# mainboard.net
KiCad netlist of a schematic drawn in EAGLE
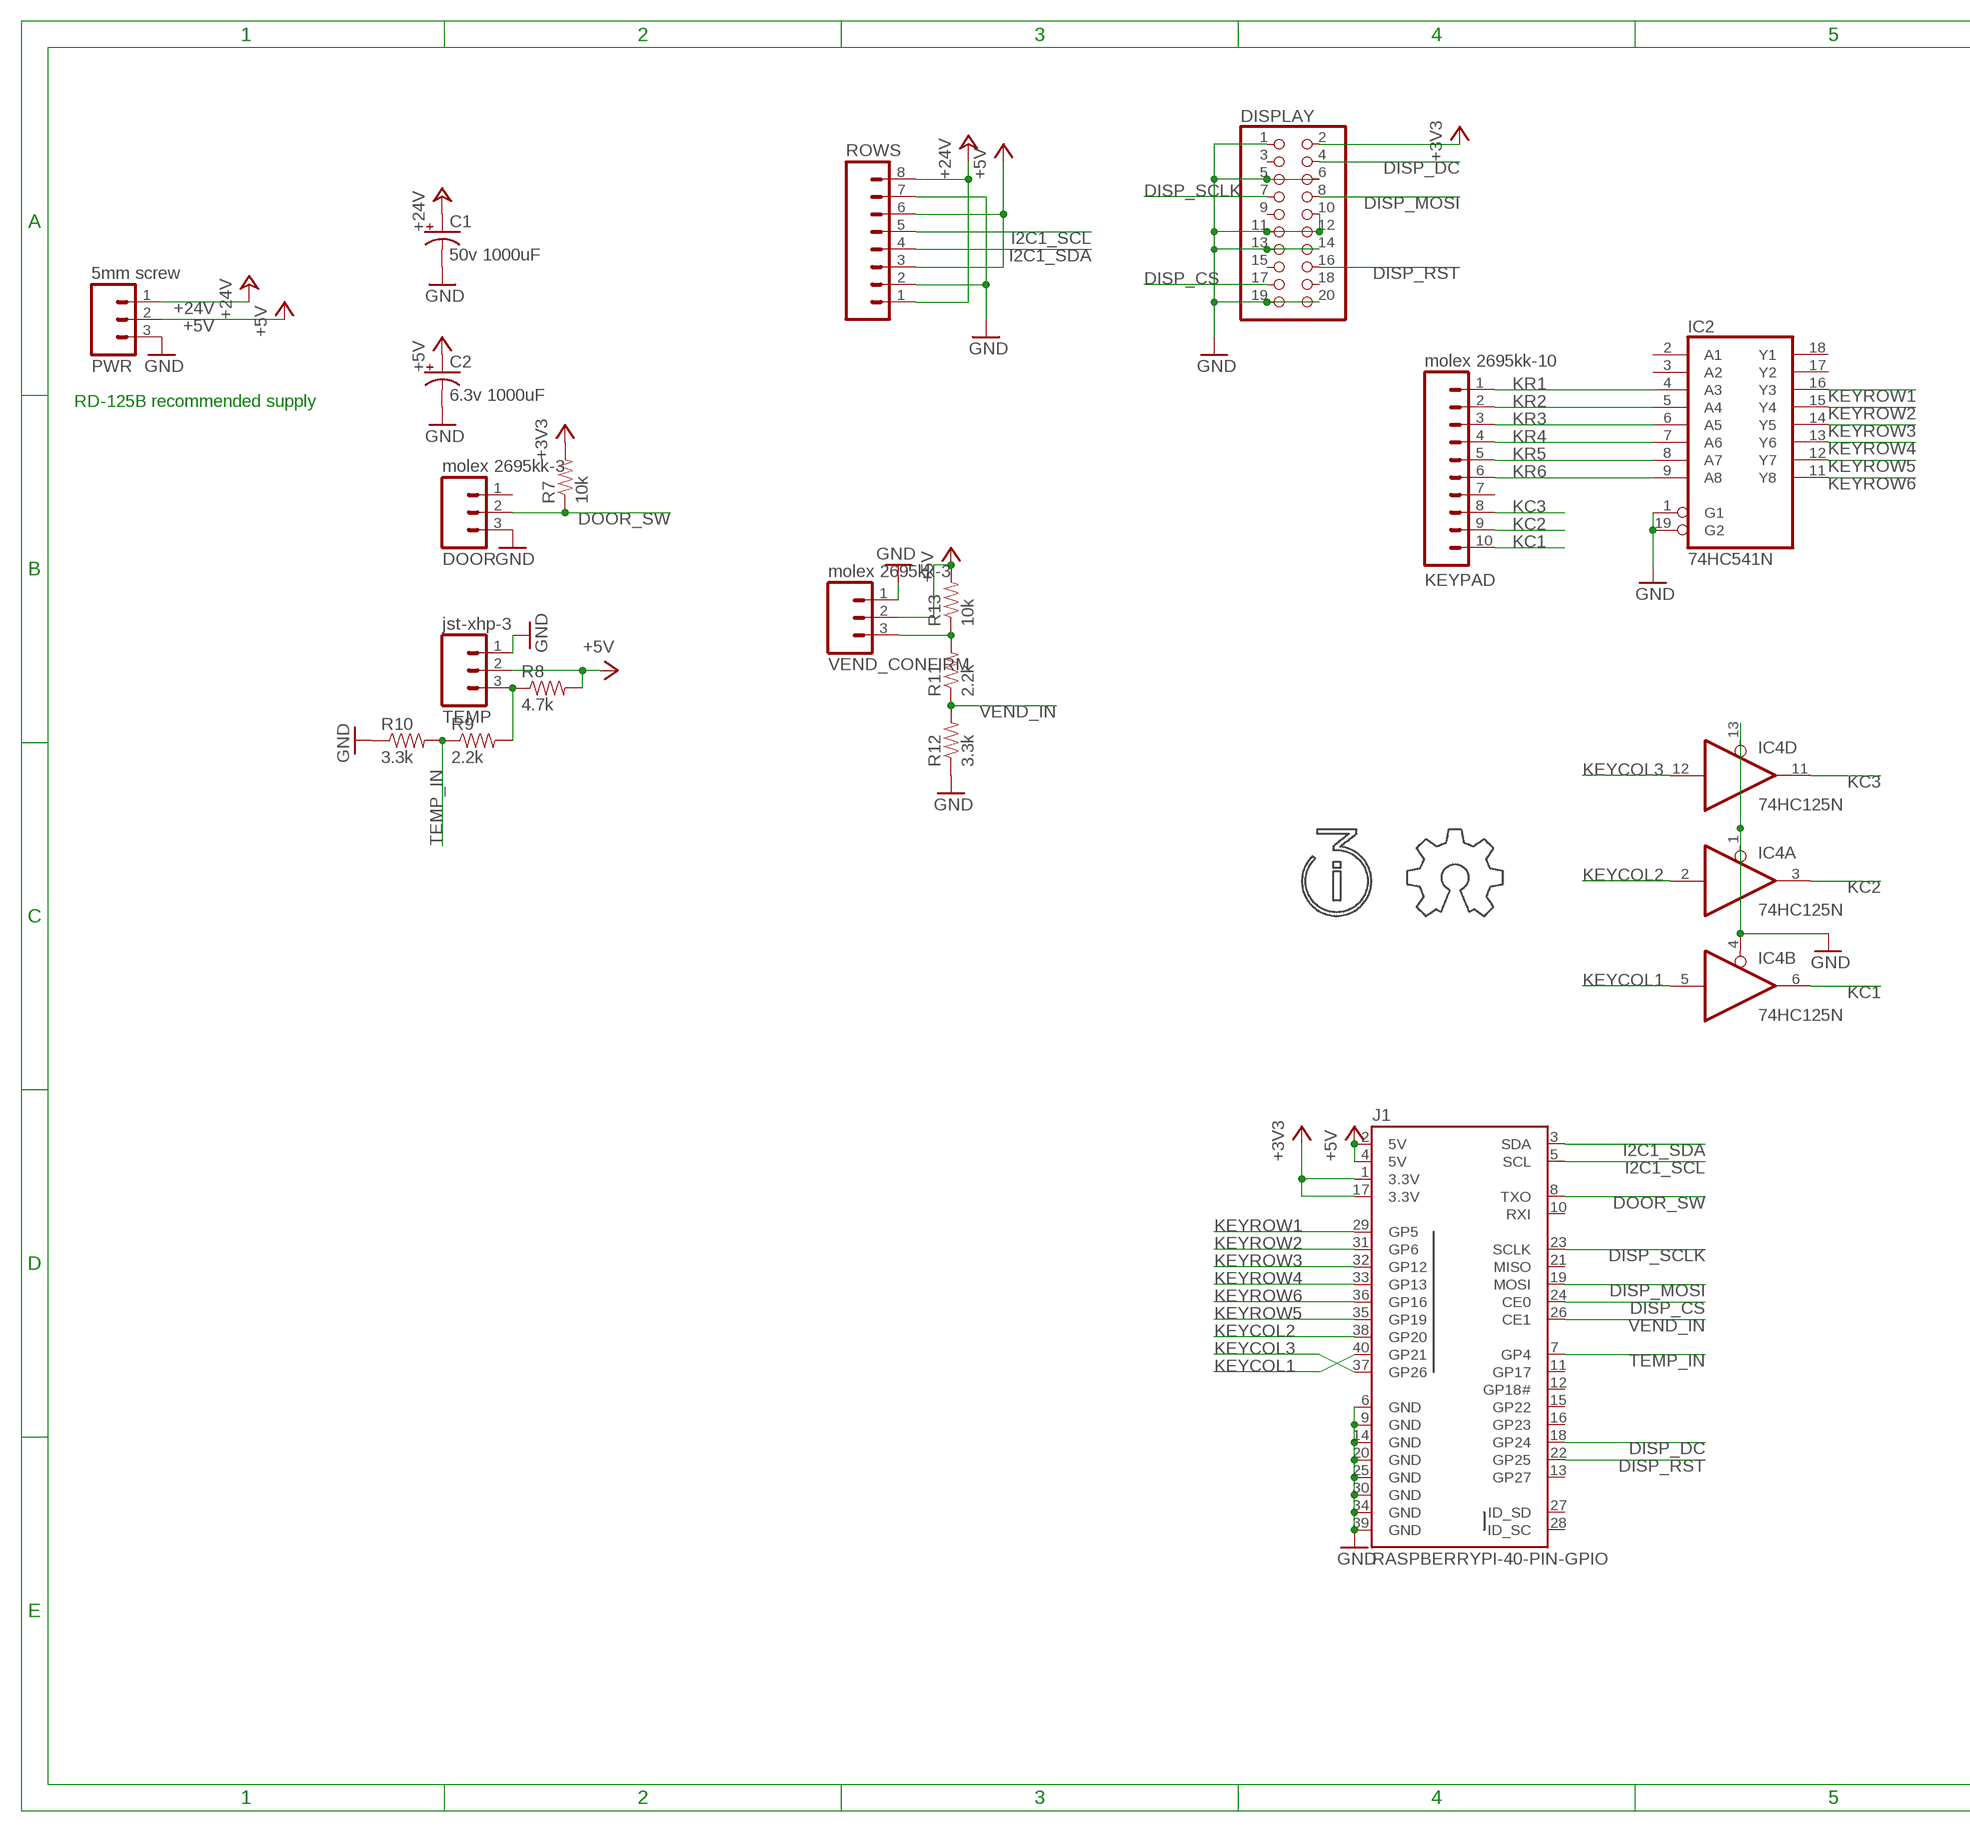
[diagram p0: schematic, sheet 1, part 1 of 2]
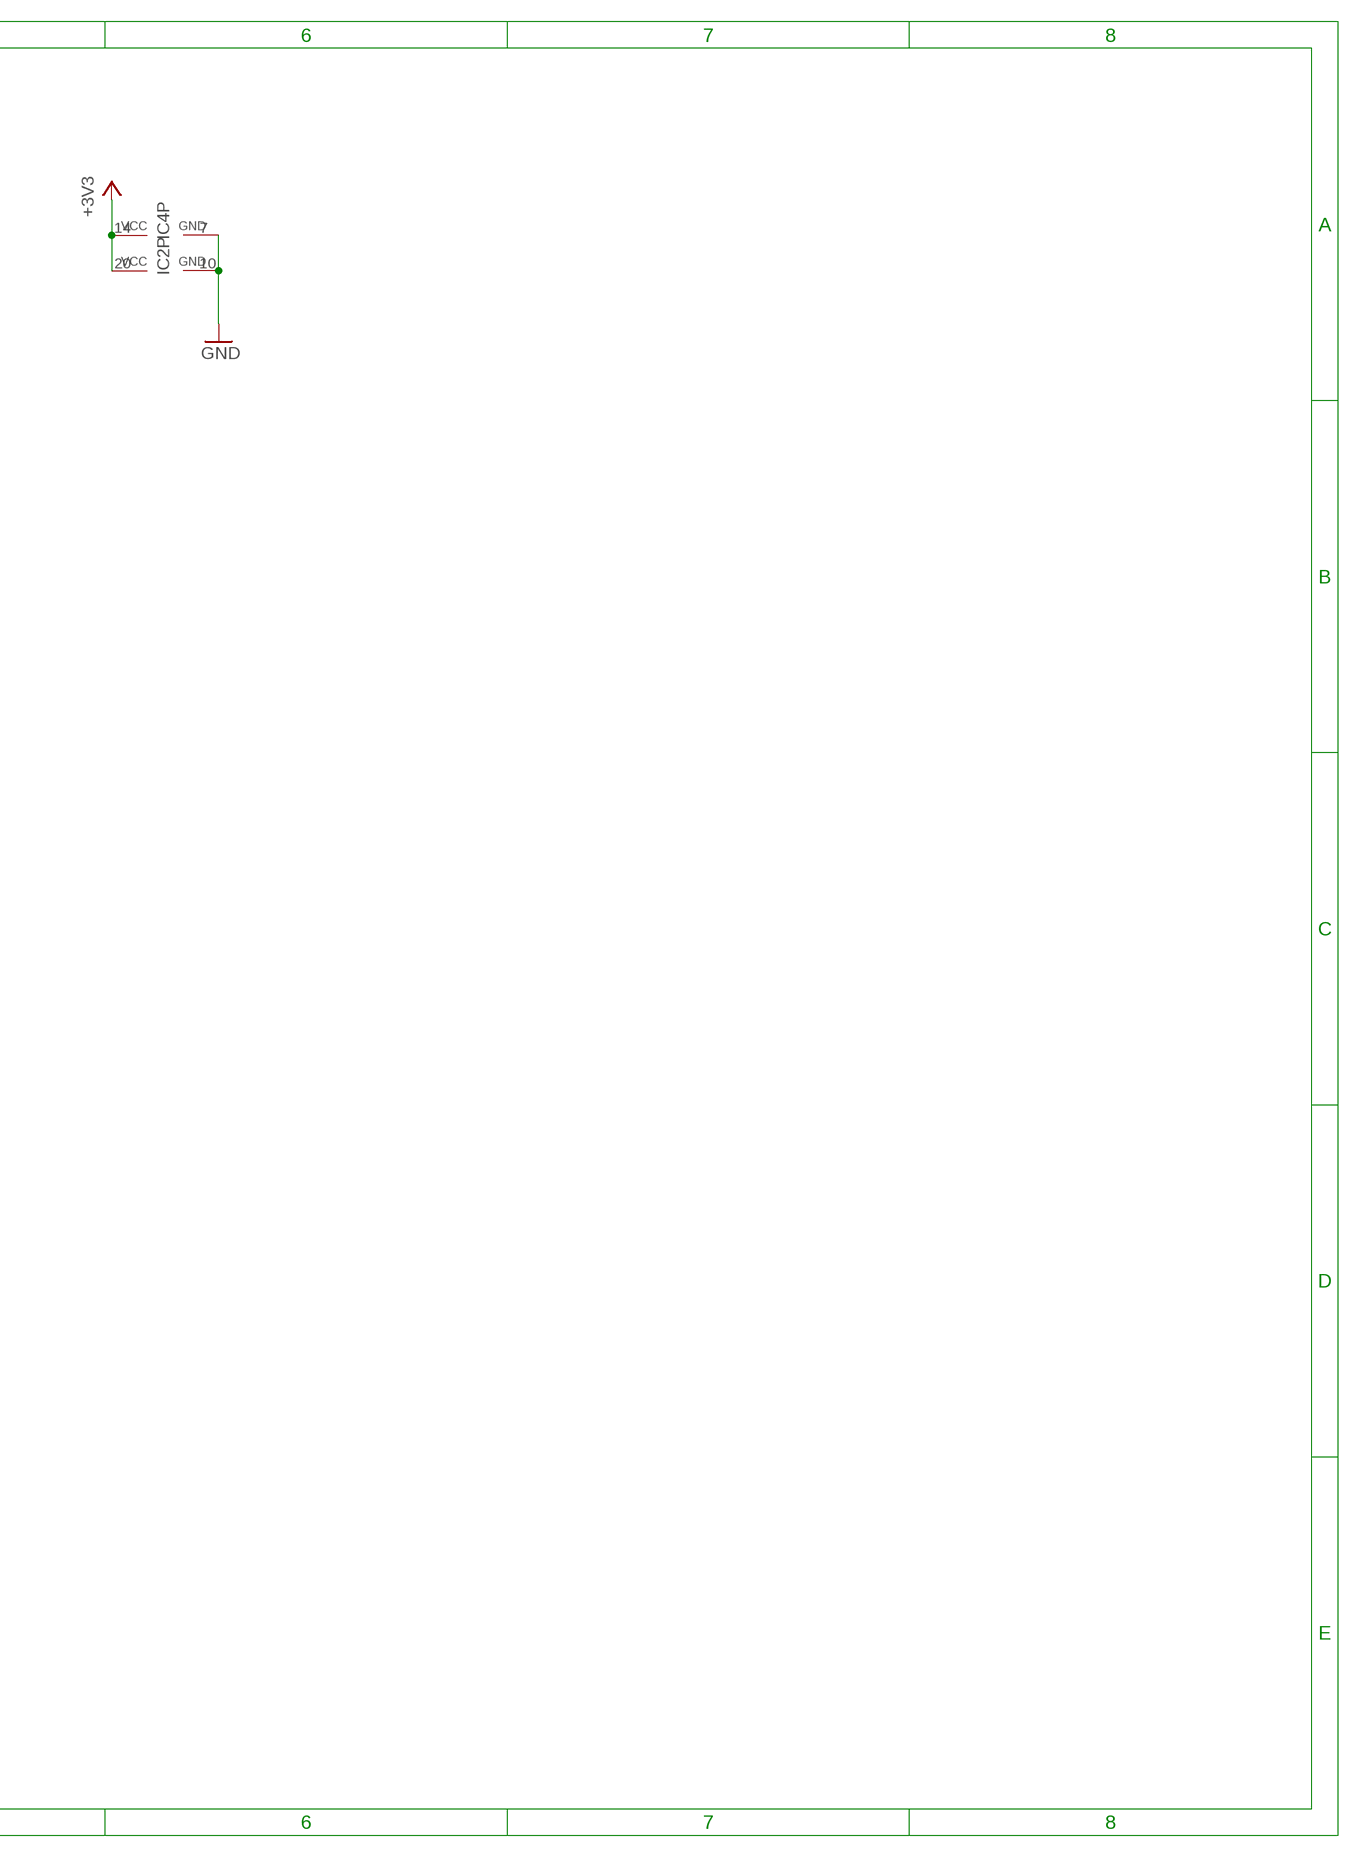
[diagram p1: schematic, sheet 1, part 2 of 2]

(export (version "E")
  (design (tool "Eeschema 10.0.6"))
  (components
    (comp (ref "C1")
      (value "50v 1000uF")
      (footprint "eagle-import:CPOL-RADIAL-1000UF-25V")
      (libsource (lib "eagle-import") (part "CAP_POLPTH4"))
    )
    (comp (ref "C2")
      (value "6.3v 1000uF")
      (footprint "eagle-import:CPOL-RADIAL-1000UF-25V")
      (libsource (lib "eagle-import") (part "CAP_POLPTH4"))
    )
    (comp (ref "DISPLAY")
      (value "PINHD-2X10")
      (footprint "eagle-import:2X10")
      (libsource (lib "eagle-import") (part "PINHD-2X10"))
    )
    (comp (ref "DOOR")
      (value "molex 2695kk-3")
      (footprint "eagle-import:MOLEX-1X3")
      (libsource (lib "eagle-import") (part "M03POLAR"))
    )
    (comp (ref "IC2")
      (value "74HC541N")
      (footprint "eagle-import:DIL20")
      (libsource (lib "eagle-import") (part "74541NHC"))
    )
    (comp (ref "IC4")
      (value "74HC125N")
      (footprint "eagle-import:DIL14")
      (libsource (lib "eagle-import") (part "74125NHC"))
    )
    (comp (ref "J1")
      (value "RASPBERRYPI-40-PIN-GPIO")
      (footprint "eagle-import:2X20-SHROUDED")
      (libsource (lib "eagle-import") (part "RASPBERRYPI-40-PIN-GPIO"))
    )
    (comp (ref "KEYPAD")
      (value "molex 2695kk-10")
      (footprint "eagle-import:1X10_LOCK")
      (libsource (lib "eagle-import") (part "M10LOCK"))
    )
    (comp (ref "PWR")
      (value "5mm screw")
      (footprint "eagle-import:SCREWTERMINAL-5MM-3")
      (libsource (lib "eagle-import") (part "M03-SCREW-5MM"))
    )
    (comp (ref "R7")
      (value "10k")
      (footprint "eagle-import:1206")
      (libsource (lib "eagle-import") (part "RESISTOR1206"))
    )
    (comp (ref "R8")
      (value "4.7k")
      (footprint "eagle-import:1206")
      (libsource (lib "eagle-import") (part "RESISTOR1206"))
    )
    (comp (ref "R9")
      (value "2.2k")
      (footprint "eagle-import:1206")
      (libsource (lib "eagle-import") (part "RESISTOR1206"))
    )
    (comp (ref "R10")
      (value "3.3k")
      (footprint "eagle-import:1206")
      (libsource (lib "eagle-import") (part "RESISTOR1206"))
    )
    (comp (ref "R11")
      (value "2.2k")
      (footprint "eagle-import:1206")
      (libsource (lib "eagle-import") (part "RESISTOR1206"))
    )
    (comp (ref "R12")
      (value "3.3k")
      (footprint "eagle-import:1206")
      (libsource (lib "eagle-import") (part "RESISTOR1206"))
    )
    (comp (ref "R13")
      (value "10k")
      (footprint "eagle-import:1206")
      (libsource (lib "eagle-import") (part "RESISTOR1206"))
    )
    (comp (ref "ROWS")
      (value "M08FEMALE_LOCK")
      (footprint "eagle-import:1X08_FEMALE_LOCK")
      (libsource (lib "eagle-import") (part "M08FEMALE_LOCK"))
    )
    (comp (ref "TEMP")
      (value "jst-xhp-3")
      (footprint "eagle-import:1X03")
      (libsource (lib "eagle-import") (part "M03PTH"))
    )
    (comp (ref "U$1")
      (value "I3LOGO")
      (footprint "eagle-import:I3LOGO")
      (libsource (lib "eagle-import") (part "I3LOGO"))
    )
    (comp (ref "U$2")
      (value "OSHWLOGO")
      (footprint "eagle-import:OSHWLOGO")
      (libsource (lib "eagle-import") (part "OSHWLOGO"))
    )
    (comp (ref "VEND_CONFIRM")
      (value "molex 2695kk-3")
      (footprint "eagle-import:MOLEX-1X3")
      (libsource (lib "eagle-import") (part "M03POLAR"))
    )
  )
  (nets
    (net (code "1") (name "+3V3") (class "Default")
      (node (ref "DISPLAY") (pin "2") (pinfunction "2_2") (pintype "passive"))
      (node (ref "IC2") (pin "20") (pinfunction "VCC_20") (pintype "power_in"))
      (node (ref "IC4") (pin "14") (pinfunction "VCC_14") (pintype "power_in"))
      (node (ref "J1") (pin "1") (pinfunction "3.3V_1") (pintype "power_in"))
      (node (ref "J1") (pin "17") (pinfunction "3.3V_17") (pintype "power_in"))
      (node (ref "R7") (pin "2") (pinfunction "2_2") (pintype "passive"))
    )
    (net (code "2") (name "+5V") (class "Default")
      (node (ref "C2") (pin "+") (pinfunction "+_+") (pintype "passive"))
      (node (ref "J1") (pin "2") (pinfunction "5V_2") (pintype "power_in"))
      (node (ref "J1") (pin "4") (pinfunction "5V_4") (pintype "power_in"))
      (node (ref "PWR") (pin "2") (pinfunction "2_2") (pintype "passive"))
      (node (ref "R13") (pin "2") (pinfunction "2_2") (pintype "passive"))
      (node (ref "R8") (pin "2") (pinfunction "2_2") (pintype "passive"))
      (node (ref "ROWS") (pin "3") (pinfunction "3_3") (pintype "passive"))
      (node (ref "ROWS") (pin "6") (pinfunction "6_6") (pintype "passive"))
      (node (ref "TEMP") (pin "2") (pinfunction "2_2") (pintype "passive"))
      (node (ref "VEND_CONFIRM") (pin "2") (pinfunction "2_2") (pintype "passive"))
    )
    (net (code "3") (name "+24V") (class "Default")
      (node (ref "C1") (pin "+") (pinfunction "+_+") (pintype "passive"))
      (node (ref "PWR") (pin "1") (pinfunction "1_1") (pintype "passive"))
      (node (ref "ROWS") (pin "1") (pinfunction "1_1") (pintype "passive"))
      (node (ref "ROWS") (pin "8") (pinfunction "8_8") (pintype "passive"))
    )
    (net (code "4") (name "/DISP_CS") (class "Default")
      (node (ref "DISPLAY") (pin "17") (pinfunction "17_17") (pintype "passive"))
      (node (ref "J1") (pin "24") (pinfunction "CE0_24") (pintype "output"))
    )
    (net (code "5") (name "/DISP_DC") (class "Default")
      (node (ref "DISPLAY") (pin "4") (pinfunction "4_4") (pintype "passive"))
      (node (ref "J1") (pin "18") (pinfunction "GP24_18") (pintype "bidirectional"))
    )
    (net (code "6") (name "/DISP_MOSI") (class "Default")
      (node (ref "DISPLAY") (pin "8") (pinfunction "8_8") (pintype "passive"))
      (node (ref "J1") (pin "19") (pinfunction "MOSI_19") (pintype "output"))
    )
    (net (code "7") (name "/DISP_RST") (class "Default")
      (node (ref "DISPLAY") (pin "16") (pinfunction "16_16") (pintype "passive"))
      (node (ref "J1") (pin "22") (pinfunction "GP25_22") (pintype "bidirectional"))
    )
    (net (code "8") (name "/DISP_SCLK") (class "Default")
      (node (ref "DISPLAY") (pin "7") (pinfunction "7_7") (pintype "passive"))
      (node (ref "J1") (pin "23") (pinfunction "SCLK_23") (pintype "output"))
    )
    (net (code "9") (name "/DOOR_SW") (class "Default")
      (node (ref "DOOR") (pin "2") (pinfunction "2_2") (pintype "passive"))
      (node (ref "J1") (pin "8") (pinfunction "TXO_8") (pintype "output"))
      (node (ref "R7") (pin "1") (pinfunction "1_1") (pintype "passive"))
    )
    (net (code "10") (name "/I2C1_SCL") (class "Default")
      (node (ref "J1") (pin "5") (pinfunction "SCL_5") (pintype "bidirectional"))
      (node (ref "ROWS") (pin "5") (pinfunction "5_5") (pintype "passive"))
    )
    (net (code "11") (name "/I2C1_SDA") (class "Default")
      (node (ref "J1") (pin "3") (pinfunction "SDA_3") (pintype "bidirectional"))
      (node (ref "ROWS") (pin "4") (pinfunction "4_4") (pintype "passive"))
    )
    (net (code "12") (name "/KC1") (class "Default")
      (node (ref "IC4") (pin "6") (pinfunction "O_6") (pintype "tri_state"))
      (node (ref "KEYPAD") (pin "10") (pinfunction "10_10") (pintype "passive"))
    )
    (net (code "13") (name "/KC2") (class "Default")
      (node (ref "IC4") (pin "3") (pinfunction "O_3") (pintype "tri_state"))
      (node (ref "KEYPAD") (pin "9") (pinfunction "9_9") (pintype "passive"))
    )
    (net (code "14") (name "/KC3") (class "Default")
      (node (ref "IC4") (pin "11") (pinfunction "O_11") (pintype "tri_state"))
      (node (ref "KEYPAD") (pin "8") (pinfunction "8_8") (pintype "passive"))
    )
    (net (code "15") (name "/KEYCOL1") (class "Default")
      (node (ref "IC4") (pin "5") (pinfunction "I_5") (pintype "input"))
      (node (ref "J1") (pin "40") (pinfunction "GP21_40") (pintype "bidirectional"))
    )
    (net (code "16") (name "/KEYCOL2") (class "Default")
      (node (ref "IC4") (pin "2") (pinfunction "I_2") (pintype "input"))
      (node (ref "J1") (pin "38") (pinfunction "GP20_38") (pintype "bidirectional"))
    )
    (net (code "17") (name "/KEYCOL3") (class "Default")
      (node (ref "IC4") (pin "12") (pinfunction "I_12") (pintype "input"))
      (node (ref "J1") (pin "37") (pinfunction "GP26_37") (pintype "bidirectional"))
    )
    (net (code "18") (name "/KEYROW1") (class "Default")
      (node (ref "IC2") (pin "16") (pinfunction "Y3_16") (pintype "tri_state"))
      (node (ref "J1") (pin "29") (pinfunction "GP5_29") (pintype "bidirectional"))
    )
    (net (code "19") (name "/KEYROW2") (class "Default")
      (node (ref "IC2") (pin "15") (pinfunction "Y4_15") (pintype "tri_state"))
      (node (ref "J1") (pin "31") (pinfunction "GP6_31") (pintype "bidirectional"))
    )
    (net (code "20") (name "/KEYROW3") (class "Default")
      (node (ref "IC2") (pin "14") (pinfunction "Y5_14") (pintype "tri_state"))
      (node (ref "J1") (pin "32") (pinfunction "GP12_32") (pintype "bidirectional"))
    )
    (net (code "21") (name "/KEYROW4") (class "Default")
      (node (ref "IC2") (pin "13") (pinfunction "Y6_13") (pintype "tri_state"))
      (node (ref "J1") (pin "33") (pinfunction "GP13_33") (pintype "bidirectional"))
    )
    (net (code "22") (name "/KEYROW5") (class "Default")
      (node (ref "IC2") (pin "12") (pinfunction "Y7_12") (pintype "tri_state"))
      (node (ref "J1") (pin "35") (pinfunction "GP19_35") (pintype "bidirectional"))
    )
    (net (code "23") (name "/KEYROW6") (class "Default")
      (node (ref "IC2") (pin "11") (pinfunction "Y8_11") (pintype "tri_state"))
      (node (ref "J1") (pin "36") (pinfunction "GP16_36") (pintype "bidirectional"))
    )
    (net (code "24") (name "/KR1") (class "Default")
      (node (ref "IC2") (pin "4") (pinfunction "A3_4") (pintype "input"))
      (node (ref "KEYPAD") (pin "1") (pinfunction "1_1") (pintype "passive"))
    )
    (net (code "25") (name "/KR2") (class "Default")
      (node (ref "IC2") (pin "5") (pinfunction "A4_5") (pintype "input"))
      (node (ref "KEYPAD") (pin "2") (pinfunction "2_2") (pintype "passive"))
    )
    (net (code "26") (name "/KR3") (class "Default")
      (node (ref "IC2") (pin "6") (pinfunction "A5_6") (pintype "input"))
      (node (ref "KEYPAD") (pin "3") (pinfunction "3_3") (pintype "passive"))
    )
    (net (code "27") (name "/KR4") (class "Default")
      (node (ref "IC2") (pin "7") (pinfunction "A6_7") (pintype "input"))
      (node (ref "KEYPAD") (pin "4") (pinfunction "4_4") (pintype "passive"))
    )
    (net (code "28") (name "/KR5") (class "Default")
      (node (ref "IC2") (pin "8") (pinfunction "A7_8") (pintype "input"))
      (node (ref "KEYPAD") (pin "5") (pinfunction "5_5") (pintype "passive"))
    )
    (net (code "29") (name "/KR6") (class "Default")
      (node (ref "IC2") (pin "9") (pinfunction "A8_9") (pintype "input"))
      (node (ref "KEYPAD") (pin "6") (pinfunction "6_6") (pintype "passive"))
    )
    (net (code "30") (name "/TEMP_IN") (class "Default")
      (node (ref "J1") (pin "7") (pinfunction "GP4_7") (pintype "bidirectional"))
      (node (ref "R10") (pin "2") (pinfunction "2_2") (pintype "passive"))
      (node (ref "R9") (pin "1") (pinfunction "1_1") (pintype "passive"))
    )
    (net (code "31") (name "/VEND_IN") (class "Default")
      (node (ref "J1") (pin "26") (pinfunction "CE1_26") (pintype "output"))
      (node (ref "R11") (pin "1") (pinfunction "1_1") (pintype "passive"))
      (node (ref "R12") (pin "2") (pinfunction "2_2") (pintype "passive"))
    )
    (net (code "32") (name "GND") (class "Default")
      (node (ref "C1") (pin "-") (pinfunction "-_-") (pintype "passive"))
      (node (ref "C2") (pin "-") (pinfunction "-_-") (pintype "passive"))
      (node (ref "DISPLAY") (pin "1") (pinfunction "1_1") (pintype "passive"))
      (node (ref "DISPLAY") (pin "10") (pinfunction "10_10") (pintype "passive"))
      (node (ref "DISPLAY") (pin "11") (pinfunction "11_11") (pintype "passive"))
      (node (ref "DISPLAY") (pin "12") (pinfunction "12_12") (pintype "passive"))
      (node (ref "DISPLAY") (pin "13") (pinfunction "13_13") (pintype "passive"))
      (node (ref "DISPLAY") (pin "14") (pinfunction "14_14") (pintype "passive"))
      (node (ref "DISPLAY") (pin "19") (pinfunction "19_19") (pintype "passive"))
      (node (ref "DISPLAY") (pin "20") (pinfunction "20_20") (pintype "passive"))
      (node (ref "DISPLAY") (pin "5") (pinfunction "5_5") (pintype "passive"))
      (node (ref "DISPLAY") (pin "6") (pinfunction "6_6") (pintype "passive"))
      (node (ref "DOOR") (pin "3") (pinfunction "3_3") (pintype "passive"))
      (node (ref "IC2") (pin "1") (pinfunction "G1_1") (pintype "input"))
      (node (ref "IC2") (pin "10") (pinfunction "GND_10") (pintype "power_in"))
      (node (ref "IC2") (pin "19") (pinfunction "G2_19") (pintype "input"))
      (node (ref "IC4") (pin "1") (pinfunction "OE_1") (pintype "input"))
      (node (ref "IC4") (pin "13") (pinfunction "OE_13") (pintype "input"))
      (node (ref "IC4") (pin "4") (pinfunction "OE_4") (pintype "input"))
      (node (ref "IC4") (pin "7") (pinfunction "GND_7") (pintype "power_in"))
      (node (ref "J1") (pin "14") (pinfunction "GND_14") (pintype "power_in"))
      (node (ref "J1") (pin "20") (pinfunction "GND_20") (pintype "power_in"))
      (node (ref "J1") (pin "25") (pinfunction "GND_25") (pintype "power_in"))
      (node (ref "J1") (pin "30") (pinfunction "GND_30") (pintype "power_in"))
      (node (ref "J1") (pin "34") (pinfunction "GND_34") (pintype "power_in"))
      (node (ref "J1") (pin "39") (pinfunction "GND_39") (pintype "power_in"))
      (node (ref "J1") (pin "6") (pinfunction "GND_6") (pintype "power_in"))
      (node (ref "J1") (pin "9") (pinfunction "GND_9") (pintype "power_in"))
      (node (ref "PWR") (pin "3") (pinfunction "3_3") (pintype "passive"))
      (node (ref "R10") (pin "1") (pinfunction "1_1") (pintype "passive"))
      (node (ref "R12") (pin "1") (pinfunction "1_1") (pintype "passive"))
      (node (ref "ROWS") (pin "2") (pinfunction "2_2") (pintype "passive"))
      (node (ref "ROWS") (pin "7") (pinfunction "7_7") (pintype "passive"))
      (node (ref "TEMP") (pin "1") (pinfunction "1_1") (pintype "passive"))
      (node (ref "VEND_CONFIRM") (pin "1") (pinfunction "1_1") (pintype "passive"))
    )
    (net (code "33") (name "Net-(R8-Pad1)") (class "Default")
      (node (ref "R8") (pin "1") (pinfunction "1_1") (pintype "passive"))
      (node (ref "R9") (pin "2") (pinfunction "2_2") (pintype "passive"))
      (node (ref "TEMP") (pin "3") (pinfunction "3_3") (pintype "passive"))
    )
    (net (code "34") (name "Net-(R11-Pad2)") (class "Default")
      (node (ref "R11") (pin "2") (pinfunction "2_2") (pintype "passive"))
      (node (ref "R13") (pin "1") (pinfunction "1_1") (pintype "passive"))
      (node (ref "VEND_CONFIRM") (pin "3") (pinfunction "3_3") (pintype "passive"))
    )
    (net (code "35") (name "unconnected-(DISPLAY-Pad3)") (class "Default")
      (node (ref "DISPLAY") (pin "3") (pinfunction "3_3") (pintype "passive"))
    )
    (net (code "36") (name "unconnected-(DISPLAY-Pad9)") (class "Default")
      (node (ref "DISPLAY") (pin "9") (pinfunction "9_9") (pintype "passive"))
    )
    (net (code "37") (name "unconnected-(DISPLAY-Pad15)") (class "Default")
      (node (ref "DISPLAY") (pin "15") (pinfunction "15_15") (pintype "passive"))
    )
    (net (code "38") (name "unconnected-(DISPLAY-Pad18)") (class "Default")
      (node (ref "DISPLAY") (pin "18") (pinfunction "18_18") (pintype "passive"))
    )
    (net (code "39") (name "unconnected-(DOOR-Pad1)") (class "Default")
      (node (ref "DOOR") (pin "1") (pinfunction "1_1") (pintype "passive"))
    )
    (net (code "40") (name "unconnected-(IC2A-A1-Pad2)") (class "Default")
      (node (ref "IC2") (pin "2") (pinfunction "A1_2") (pintype "input"))
    )
    (net (code "41") (name "unconnected-(IC2A-A2-Pad3)") (class "Default")
      (node (ref "IC2") (pin "3") (pinfunction "A2_3") (pintype "input"))
    )
    (net (code "42") (name "unconnected-(IC2A-Y1-Pad18)") (class "Default")
      (node (ref "IC2") (pin "18") (pinfunction "Y1_18") (pintype "tri_state"))
    )
    (net (code "43") (name "unconnected-(IC2A-Y2-Pad17)") (class "Default")
      (node (ref "IC2") (pin "17") (pinfunction "Y2_17") (pintype "tri_state"))
    )
    (net (code "44") (name "unconnected-(J1-GP17-Pad11)") (class "Default")
      (node (ref "J1") (pin "11") (pinfunction "GP17_11") (pintype "bidirectional"))
    )
    (net (code "45") (name "unconnected-(J1-GP18#-Pad12)") (class "Default")
      (node (ref "J1") (pin "12") (pinfunction "GP18#_12") (pintype "bidirectional"))
    )
    (net (code "46") (name "unconnected-(J1-GP22-Pad15)") (class "Default")
      (node (ref "J1") (pin "15") (pinfunction "GP22_15") (pintype "bidirectional"))
    )
    (net (code "47") (name "unconnected-(J1-GP23-Pad16)") (class "Default")
      (node (ref "J1") (pin "16") (pinfunction "GP23_16") (pintype "bidirectional"))
    )
    (net (code "48") (name "unconnected-(J1-GP27-Pad13)") (class "Default")
      (node (ref "J1") (pin "13") (pinfunction "GP27_13") (pintype "bidirectional"))
    )
    (net (code "49") (name "unconnected-(J1-ID_SC-Pad28)") (class "Default")
      (node (ref "J1") (pin "28") (pinfunction "ID_SC_28") (pintype "bidirectional"))
    )
    (net (code "50") (name "unconnected-(J1-ID_SD-Pad27)") (class "Default")
      (node (ref "J1") (pin "27") (pinfunction "ID_SD_27") (pintype "bidirectional"))
    )
    (net (code "51") (name "unconnected-(J1-MISO-Pad21)") (class "Default")
      (node (ref "J1") (pin "21") (pinfunction "MISO_21") (pintype "input"))
    )
    (net (code "52") (name "unconnected-(J1-RXI-Pad10)") (class "Default")
      (node (ref "J1") (pin "10") (pinfunction "RXI_10") (pintype "input"))
    )
    (net (code "53") (name "unconnected-(KEYPAD-Pad7)") (class "Default")
      (node (ref "KEYPAD") (pin "7") (pinfunction "7_7") (pintype "passive"))
    )
  )
)
